# 2V_REG.net
KiCad netlist of a schematic drawn in Altium Designer
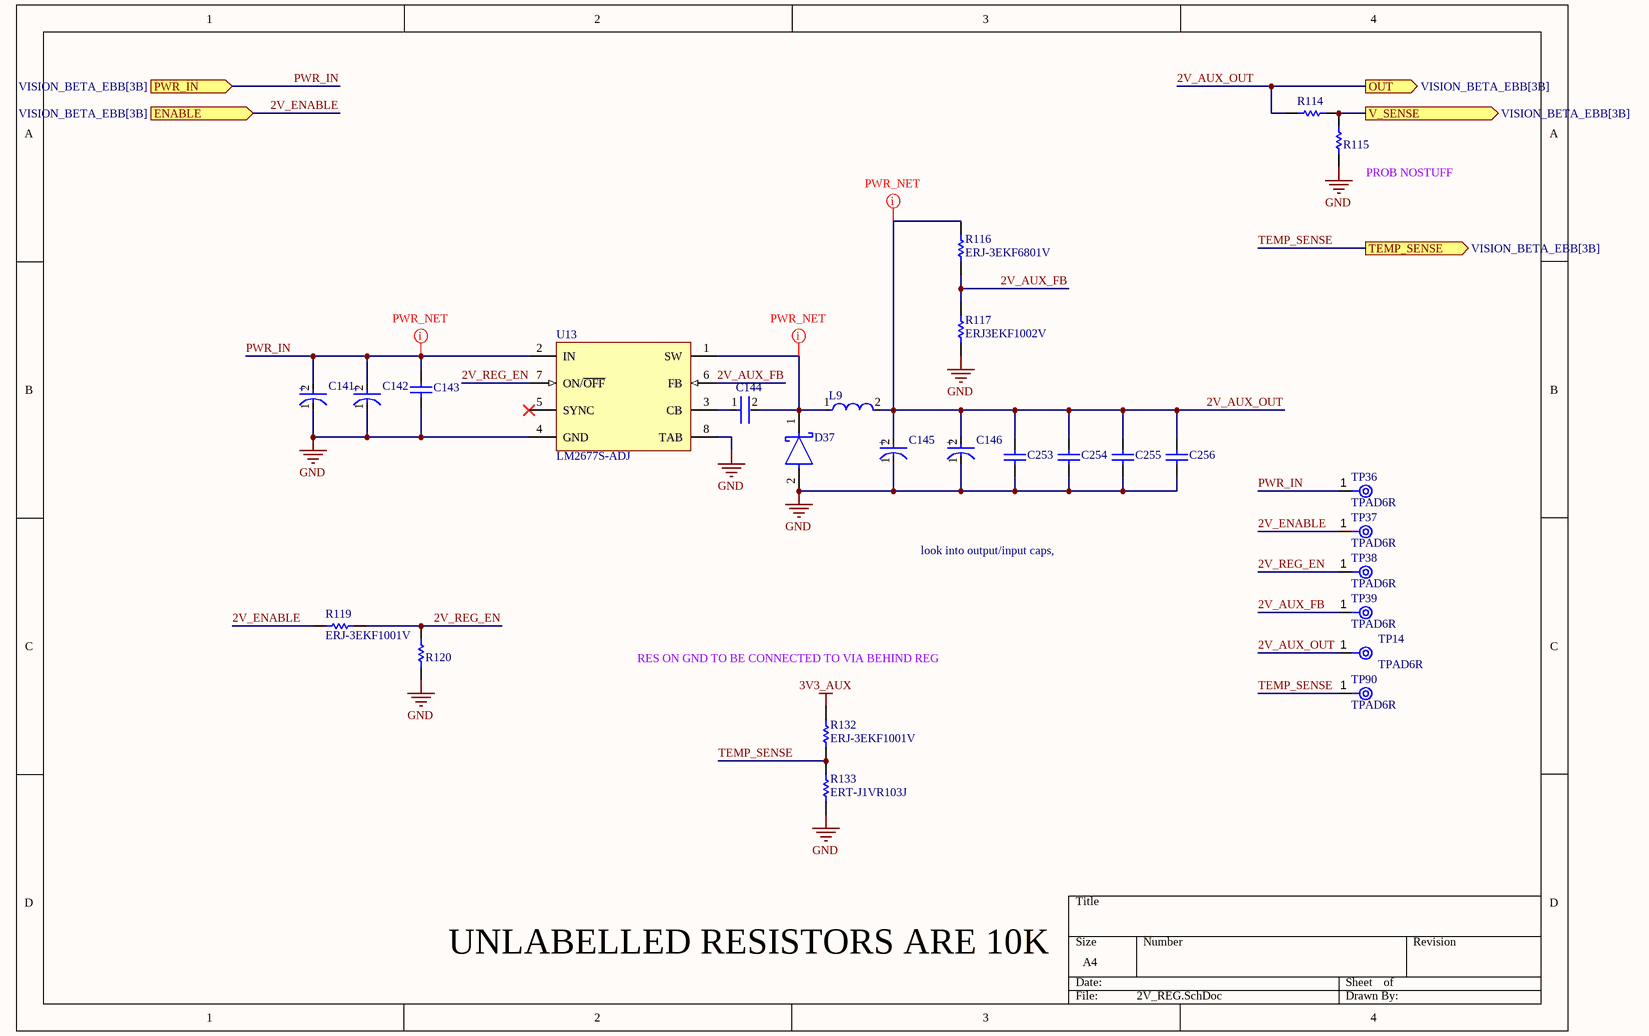
[diagram p0: 2V_REG.SchDoc]

(export (version "E")
  (design (tool "Eeschema 10.0.6"))
  (components
    (comp (ref "C141")
      (value "EEHZA1V680XP")
      (footprint "FP-EEH-D8-MFG")
      (description "Conductive Polymer Hybrid Aluminum Electrolytic Capacitors 68uF ±20% 35V RADIAL SMT 6.3x7.7mm")
      (fields (field (name "VOLTAGE") "35V") (field (name "TOLERANCE") "20%"))
      (libsource (lib "Altium Content Vault") (part "a00bbbee19879c290e62620ae7e47b1"))
    )
    (comp (ref "C142")
      (value "EEHZA1V680XP")
      (footprint "FP-EEH-D8-MFG")
      (description "Conductive Polymer Hybrid Aluminum Electrolytic Capacitors 68uF ±20% 35V RADIAL SMT 6.3x7.7mm")
      (fields (field (name "VOLTAGE") "35V") (field (name "TOLERANCE") "20%"))
      (libsource (lib "Altium Content Vault") (part "a00bbbee19879c290e62620ae7e47b1"))
    )
    (comp (ref "C143")
      (value "CAP 470nF 50V 1812(4532)")
      (footprint "CAPC1812(4532)125_M")
      (description "CAP 470nF 50V ±10% 1812 (4532 Metric) Thickness 1.25mm SMD")
      (fields (field (name "TOLERANCE") "Â±10%"))
      (libsource (lib "Altium Content Vault") (part "CAP"))
    )
    (comp (ref "C144")
      (value "C0805C103J5RACTU")
      (footprint "FP-C0805C-DN-MFG")
      (description "CAP CER 10000PF 50V X7R 0805")
      (fields
        (field (name "MANUFACTURER") "KEMET")
        (field (name "OCTOPART") "https://octopart.com/c0805c103j5ractu-kemet-133473")
      )
      (libsource (lib "Altium Content Vault") (part "b4654b650e69147ec39a6b967a45e02"))
    )
    (comp (ref "C145")
      (value "16SVPC120M")
      (footprint "FP-OS-CON-SMT-E7-MFG")
      (description "Conductive Polymer Aluminum Solid Capacitors (OS-CON) 120uF ±20% 16V RADIAL SMT 8x6.9mm")
      (fields (field (name "VOLTAGE") "16V") (field (name "TOLERANCE") "20%"))
      (libsource (lib "Altium Content Vault") (part "cf48714ba7e38822c1575c7ec0b6d1f"))
    )
    (comp (ref "C146")
      (value "16SVPC120M")
      (footprint "FP-OS-CON-SMT-E7-MFG")
      (description "Conductive Polymer Aluminum Solid Capacitors (OS-CON) 120uF ±20% 16V RADIAL SMT 8x6.9mm")
      (fields (field (name "VOLTAGE") "16V") (field (name "TOLERANCE") "20%"))
      (libsource (lib "Altium Content Vault") (part "cf48714ba7e38822c1575c7ec0b6d1f"))
    )
    (comp (ref "C253")
      (value "CAP 470nF 50V 1812(4532)")
      (footprint "CAPC1812(4532)125_M")
      (description "CAP 470nF 50V ±10% 1812 (4532 Metric) Thickness 1.25mm SMD")
      (fields (field (name "TOLERANCE") "Â±10%"))
      (libsource (lib "Altium Content Vault") (part "CAP"))
    )
    (comp (ref "C254")
      (value "CAP 470nF 50V 1812(4532)")
      (footprint "CAPC1812(4532)125_M")
      (description "CAP 470nF 50V ±10% 1812 (4532 Metric) Thickness 1.25mm SMD")
      (fields (field (name "TOLERANCE") "Â±10%"))
      (libsource (lib "Altium Content Vault") (part "CAP"))
    )
    (comp (ref "C255")
      (value "CAP 470nF 50V 1812(4532)")
      (footprint "CAPC1812(4532)125_M")
      (description "CAP 470nF 50V ±10% 1812 (4532 Metric) Thickness 1.25mm SMD")
      (fields (field (name "TOLERANCE") "Â±10%"))
      (libsource (lib "Altium Content Vault") (part "CAP"))
    )
    (comp (ref "C256")
      (value "CAP 470nF 50V 1812(4532)")
      (footprint "CAPC1812(4532)125_M")
      (description "CAP 470nF 50V ±10% 1812 (4532 Metric) Thickness 1.25mm SMD")
      (fields (field (name "TOLERANCE") "Â±10%"))
      (libsource (lib "Altium Content Vault") (part "CAP"))
    )
    (comp (ref "D37")
      (value "B540C-13-F")
      (footprint "FP-SMC-MFG")
      (description "DIODE SCHOTTKY 40V 5A SMC")
      (fields
        (field (name "OCTOPART") "https://octopart.com/b540c-13-f-diodes+inc.-325873")
        (field (name "MANUFACTURER") "Diodes Inc.")
      )
      (libsource (lib "Altium Content Vault") (part "1d6ec82d83fb6aee721767c19dac4b9"))
    )
    (comp (ref "L9")
      (value "SRR1260-150M")
      (footprint "FP-SRR1260-MFG")
      (description "FIXED IND 15UH 5A 27 MOHM SMD")
      (fields (field (name "TOLERANCE") "20%"))
      (libsource (lib "Altium Content Vault") (part "725321dda6339637d4d059423bc1c3c"))
    )
    (comp (ref "R114")
      (value "ERJ3EKF1002V")
      (footprint "RESC1609X55X30LL15T15")
      (description "Chip Resistor, 10 KOhm, +/- 1%, 0.1 W, -55 to 155 degC, 0603 (1608 Metric), RoHS, Tape and Reel")
      (fields (field (name "TOLERANCE") "1%") (field (name "MANUFACTURER") "Panasonic"))
      (libsource (lib "Altium Content Vault") (part "RES-2"))
    )
    (comp (ref "R115")
      (value "ERJ3EKF1002V")
      (footprint "RESC1609X55X30LL15T15")
      (description "Chip Resistor, 10 KOhm, +/- 1%, 0.1 W, -55 to 155 degC, 0603 (1608 Metric), RoHS, Tape and Reel")
      (fields (field (name "TOLERANCE") "1%") (field (name "MANUFACTURER") "Panasonic"))
      (libsource (lib "Altium Content Vault") (part "RES-2"))
    )
    (comp (ref "R116")
      (value "ERJ-3EKF6801V")
      (footprint "RESC1609X55X30NL15T15")
      (description "Chip Resistor, 6.8 KOhm, +/- 1%, 0.1 W, -55 to 155 degC, 0603 (1608 Metric), RoHS, Tape and Reel")
      (libsource (lib "Altium Content Vault") (part "RES-2"))
    )
    (comp (ref "R117")
      (value "ERJ3EKF1002V")
      (footprint "RESC1609X55X30LL15T15")
      (description "Chip Resistor, 10 KOhm, +/- 1%, 0.1 W, -55 to 155 degC, 0603 (1608 Metric), RoHS, Tape and Reel")
      (fields (field (name "TOLERANCE") "1%") (field (name "MANUFACTURER") "Panasonic"))
      (libsource (lib "Altium Content Vault") (part "RES-2"))
    )
    (comp (ref "R119")
      (value "ERJ-3EKF1001V")
      (footprint "RESC1608X55X30LL15T15")
      (fields (field (name "MANUFACTURER") "Panasonic"))
      (libsource (lib "Altium Content Vault") (part "RES"))
    )
    (comp (ref "R120")
      (value "ERJ3EKF1002V")
      (footprint "RESC1609X55X30LL15T15")
      (description "Chip Resistor, 10 KOhm, +/- 1%, 0.1 W, -55 to 155 degC, 0603 (1608 Metric), RoHS, Tape and Reel")
      (fields (field (name "TOLERANCE") "1%") (field (name "MANUFACTURER") "Panasonic"))
      (libsource (lib "Altium Content Vault") (part "RES-2"))
    )
    (comp (ref "R132")
      (value "ERJ-3EKF1001V")
      (footprint "RESC1608X55X30LL15T15")
      (fields (field (name "MANUFACTURER") "Panasonic"))
      (libsource (lib "Altium Content Vault") (part "RES"))
    )
    (comp (ref "R133")
      (value "ERT-J1VR103J")
      (footprint "RESC1608X90X30ML15T20")
      (fields (field (name "MANUFACTURER") "Panasonic"))
      (libsource (lib "Altium Content Vault") (part "RES"))
    )
    (comp (ref "TP14")
      (value "TPAD6R")
      (footprint "New footprint 1")
      (description "Test Point .6mm")
      (libsource (lib "Space Concordia") (part "TP"))
    )
    (comp (ref "TP36")
      (value "TPAD6R")
      (footprint "New footprint 1")
      (description "Test Point .6mm")
      (libsource (lib "Space Concordia") (part "TP"))
    )
    (comp (ref "TP37")
      (value "TPAD6R")
      (footprint "New footprint 1")
      (description "Test Point .6mm")
      (libsource (lib "Space Concordia") (part "TP"))
    )
    (comp (ref "TP38")
      (value "TPAD6R")
      (footprint "New footprint 1")
      (description "Test Point .6mm")
      (libsource (lib "Space Concordia") (part "TP"))
    )
    (comp (ref "TP39")
      (value "TPAD6R")
      (footprint "New footprint 1")
      (description "Test Point .6mm")
      (libsource (lib "Space Concordia") (part "TP"))
    )
    (comp (ref "TP90")
      (value "TPAD6R")
      (footprint "New footprint 1")
      (description "Test Point .6mm")
      (libsource (lib "Space Concordia") (part "TP"))
    )
    (comp (ref "U13")
      (value "LM2677S-ADJ")
      (footprint "KTW0007B_M")
      (description "SIMPLE SWITCHER® High Efficiency 5A Step-Down Voltage Regulator with Sync, 7-pin TO-263")
      (fields (field (name "MANUFACTURER") "Texas Instruments"))
      (libsource (lib "Altium Content Vault") (part "PM-REG-LM2670S-12"))
    )
  )
  (nets
    (net (code "1") (name "/2V_AUX_FB") (class "Default")
      (node (ref "R116") (pin "1") (pinfunction "1_1") (pintype "passive"))
      (node (ref "R117") (pin "2") (pinfunction "2_2") (pintype "passive"))
      (node (ref "TP39") (pin "1") (pinfunction "TP_1") (pintype "passive"))
      (node (ref "U13") (pin "6") (pinfunction "FB_6") (pintype "input"))
    )
    (net (code "2") (name "/2V_AUX_OUT") (class "Default")
      (node (ref "C145") (pin "2") (pinfunction "A_2") (pintype "passive"))
      (node (ref "C146") (pin "2") (pinfunction "A_2") (pintype "passive"))
      (node (ref "C253") (pin "2") (pinfunction "2_2") (pintype "passive"))
      (node (ref "C254") (pin "2") (pinfunction "2_2") (pintype "passive"))
      (node (ref "C255") (pin "2") (pinfunction "2_2") (pintype "passive"))
      (node (ref "C256") (pin "2") (pinfunction "2_2") (pintype "passive"))
      (node (ref "L9") (pin "2") (pinfunction "2_2") (pintype "passive"))
      (node (ref "R114") (pin "1") (pinfunction "1_1") (pintype "passive"))
      (node (ref "R116") (pin "2") (pinfunction "2_2") (pintype "passive"))
      (node (ref "TP14") (pin "1") (pinfunction "TP_1") (pintype "passive"))
    )
    (net (code "3") (name "/2V_ENABLE") (class "Default")
      (node (ref "R119") (pin "1") (pinfunction "1_1") (pintype "passive"))
      (node (ref "TP37") (pin "1") (pinfunction "TP_1") (pintype "passive"))
    )
    (net (code "4") (name "/2V_REG_EN") (class "Default")
      (node (ref "R119") (pin "2") (pinfunction "2_2") (pintype "passive"))
      (node (ref "R120") (pin "2") (pinfunction "2_2") (pintype "passive"))
      (node (ref "TP38") (pin "1") (pinfunction "TP_1") (pintype "passive"))
      (node (ref "U13") (pin "7") (pinfunction "ON/~{OFF}_7") (pintype "input"))
    )
    (net (code "5") (name "/PWR_IN") (class "Default")
      (node (ref "C141") (pin "2") (pinfunction "A_2") (pintype "passive"))
      (node (ref "C142") (pin "2") (pinfunction "A_2") (pintype "passive"))
      (node (ref "C143") (pin "2") (pinfunction "2_2") (pintype "passive"))
      (node (ref "TP36") (pin "1") (pinfunction "TP_1") (pintype "passive"))
      (node (ref "U13") (pin "2") (pinfunction "IN_2") (pintype "power_in"))
    )
    (net (code "6") (name "/TEMP_SENSE") (class "Default")
      (node (ref "R132") (pin "1") (pinfunction "1_1") (pintype "passive"))
      (node (ref "R133") (pin "2") (pinfunction "2_2") (pintype "passive"))
      (node (ref "TP90") (pin "1") (pinfunction "TP_1") (pintype "passive"))
    )
    (net (code "7") (name "/V_SENSE") (class "Default")
      (node (ref "R114") (pin "2") (pinfunction "2_2") (pintype "passive"))
      (node (ref "R115") (pin "2") (pinfunction "2_2") (pintype "passive"))
    )
    (net (code "8") (name "3V3_AUX") (class "Default")
      (node (ref "R132") (pin "2") (pinfunction "2_2") (pintype "passive"))
    )
    (net (code "9") (name "GND") (class "Default")
      (node (ref "C141") (pin "1") (pinfunction "C_1") (pintype "passive"))
      (node (ref "C142") (pin "1") (pinfunction "C_1") (pintype "passive"))
      (node (ref "C143") (pin "1") (pinfunction "1_1") (pintype "passive"))
      (node (ref "C145") (pin "1") (pinfunction "C_1") (pintype "passive"))
      (node (ref "C146") (pin "1") (pinfunction "C_1") (pintype "passive"))
      (node (ref "C253") (pin "1") (pinfunction "1_1") (pintype "passive"))
      (node (ref "C254") (pin "1") (pinfunction "1_1") (pintype "passive"))
      (node (ref "C255") (pin "1") (pinfunction "1_1") (pintype "passive"))
      (node (ref "C256") (pin "1") (pinfunction "1_1") (pintype "passive"))
      (node (ref "D37") (pin "2") (pinfunction "A_2") (pintype "passive"))
      (node (ref "R115") (pin "1") (pinfunction "1_1") (pintype "passive"))
      (node (ref "R117") (pin "1") (pinfunction "1_1") (pintype "passive"))
      (node (ref "R120") (pin "1") (pinfunction "1_1") (pintype "passive"))
      (node (ref "R133") (pin "1") (pinfunction "1_1") (pintype "passive"))
      (node (ref "U13") (pin "4") (pinfunction "GND_4") (pintype "power_in"))
      (node (ref "U13") (pin "8") (pinfunction "TAB_8") (pintype "passive"))
    )
    (net (code "10") (name "Net-(D37-C)") (class "Default")
      (node (ref "C144") (pin "2") (pinfunction "2_2") (pintype "passive"))
      (node (ref "D37") (pin "1") (pinfunction "C_1") (pintype "passive"))
      (node (ref "L9") (pin "1") (pinfunction "1_1") (pintype "passive"))
      (node (ref "U13") (pin "1") (pinfunction "SW_1") (pintype "power_in"))
    )
    (net (code "11") (name "Net-(U13-CB)") (class "Default")
      (node (ref "C144") (pin "1") (pinfunction "1_1") (pintype "passive"))
      (node (ref "U13") (pin "3") (pinfunction "CB_3") (pintype "passive"))
    )
    (net (code "12") (name "unconnected-(U13-SYNC-Pad5)") (class "Default")
      (node (ref "U13") (pin "5") (pinfunction "SYNC_5") (pintype "passive+no_connect"))
    )
  )
)
